# v1.net
KiCad netlist of a schematic drawn in EAGLE
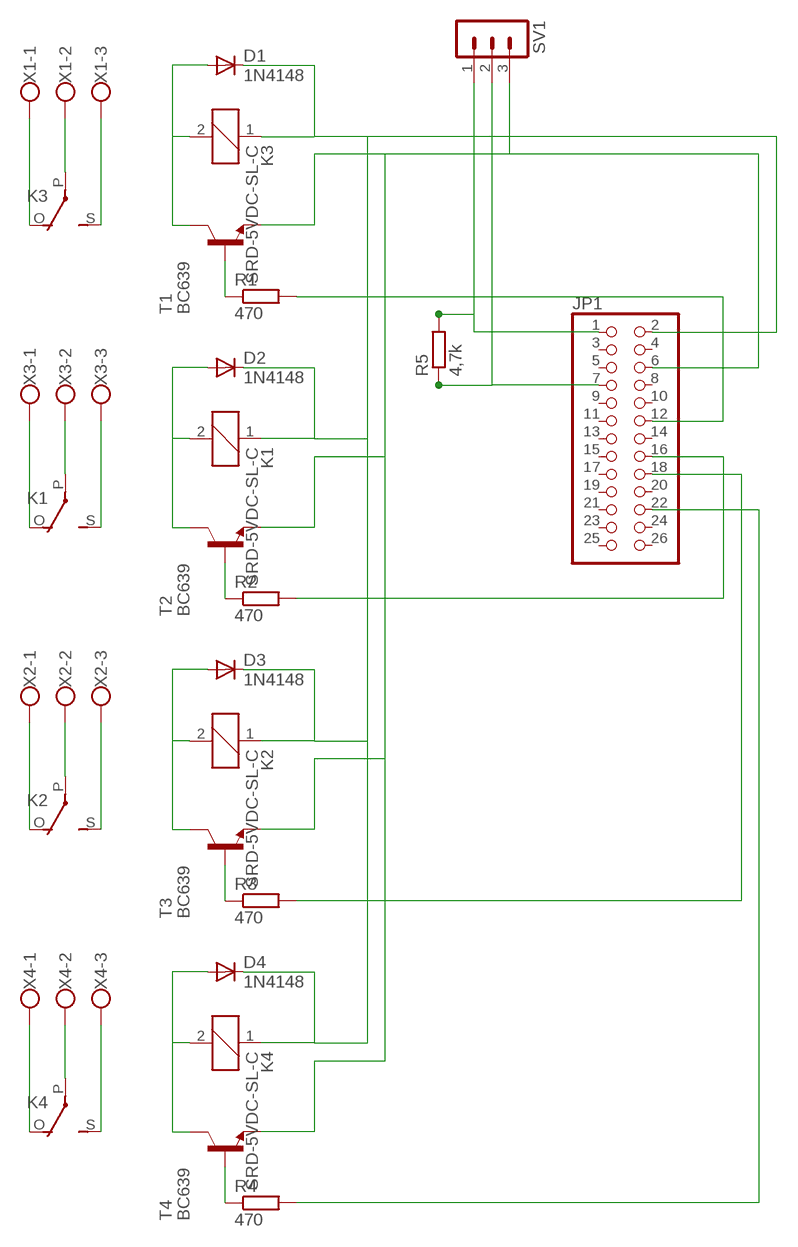
[diagram p0: schematic, sheet 1]

(export (version "E")
  (design (tool "Eeschema 10.0.6"))
  (components
    (comp (ref "D1")
      (value "1N4148")
      (footprint "eagle-import:DO41-10")
      (libsource (lib "eagle-import") (part "1N4004"))
    )
    (comp (ref "D2")
      (value "1N4148")
      (footprint "eagle-import:DO41-10")
      (libsource (lib "eagle-import") (part "1N4004"))
    )
    (comp (ref "D3")
      (value "1N4148")
      (footprint "eagle-import:DO41-10")
      (libsource (lib "eagle-import") (part "1N4004"))
    )
    (comp (ref "D4")
      (value "1N4148")
      (footprint "eagle-import:DO41-10")
      (libsource (lib "eagle-import") (part "1N4004"))
    )
    (comp (ref "JP1")
      (value "PINHD-2X13")
      (footprint "eagle-import:2X13")
      (libsource (lib "eagle-import") (part "PINHD-2X13"))
    )
    (comp (ref "K1")
      (value "SRD-5VDC-SL-C")
      (footprint "eagle-import:ZF112")
      (libsource (lib "eagle-import") (part "ZF112"))
    )
    (comp (ref "K2")
      (value "SRD-5VDC-SL-C")
      (footprint "eagle-import:ZF112")
      (libsource (lib "eagle-import") (part "ZF112"))
    )
    (comp (ref "K3")
      (value "SRD-5VDC-SL-C")
      (footprint "eagle-import:ZF112")
      (libsource (lib "eagle-import") (part "ZF112"))
    )
    (comp (ref "K4")
      (value "SRD-5VDC-SL-C")
      (footprint "eagle-import:ZF112")
      (libsource (lib "eagle-import") (part "ZF112"))
    )
    (comp (ref "R1")
      (value "470")
      (footprint "eagle-import:0204_7")
      (libsource (lib "eagle-import") (part "R-EU_0204/7"))
    )
    (comp (ref "R2")
      (value "470")
      (footprint "eagle-import:0204_7")
      (libsource (lib "eagle-import") (part "R-EU_0204/7"))
    )
    (comp (ref "R3")
      (value "470")
      (footprint "eagle-import:0204_7")
      (libsource (lib "eagle-import") (part "R-EU_0204/7"))
    )
    (comp (ref "R4")
      (value "470")
      (footprint "eagle-import:0204_7")
      (libsource (lib "eagle-import") (part "R-EU_0204/7"))
    )
    (comp (ref "R5")
      (value "4,7k")
      (footprint "eagle-import:0207_7")
      (libsource (lib "eagle-import") (part "R-EU_0207/7"))
    )
    (comp (ref "SV1")
      (value "MA03-1")
      (footprint "eagle-import:MA03-1")
      (libsource (lib "eagle-import") (part "MA03-1"))
    )
    (comp (ref "T1")
      (value "BC639")
      (footprint "eagle-import:TO92-ECB")
      (libsource (lib "eagle-import") (part "-NPN-TO92-ECBBC639"))
    )
    (comp (ref "T2")
      (value "BC639")
      (footprint "eagle-import:TO92-ECB")
      (libsource (lib "eagle-import") (part "-NPN-TO92-ECBBC639"))
    )
    (comp (ref "T3")
      (value "BC639")
      (footprint "eagle-import:TO92-ECB")
      (libsource (lib "eagle-import") (part "-NPN-TO92-ECBBC639"))
    )
    (comp (ref "T4")
      (value "BC639")
      (footprint "eagle-import:TO92-ECB")
      (libsource (lib "eagle-import") (part "-NPN-TO92-ECBBC639"))
    )
    (comp (ref "X1")
      (value "W237-103")
      (footprint "eagle-import:W237-103")
      (fields (field (name "MPN") "237-103"))
      (libsource (lib "eagle-import") (part "W237-103"))
    )
    (comp (ref "X2")
      (value "W237-103")
      (footprint "eagle-import:W237-103")
      (fields (field (name "MPN") "237-103"))
      (libsource (lib "eagle-import") (part "W237-103"))
    )
    (comp (ref "X3")
      (value "W237-103")
      (footprint "eagle-import:W237-103")
      (fields (field (name "MPN") "237-103"))
      (libsource (lib "eagle-import") (part "W237-103"))
    )
    (comp (ref "X4")
      (value "W237-103")
      (footprint "eagle-import:W237-103")
      (fields (field (name "MPN") "237-103"))
      (libsource (lib "eagle-import") (part "W237-103"))
    )
  )
  (nets
    (net (code "1") (name "Net-(D1-PadA)") (class "Default")
      (node (ref "D1") (pin "A") (pinfunction "A_A") (pintype "passive"))
      (node (ref "K3") (pin "2") (pinfunction "2_2") (pintype "passive"))
      (node (ref "T1") (pin "C") (pinfunction "C_C") (pintype "passive"))
    )
    (net (code "2") (name "Net-(D1-PadC)") (class "Default")
      (node (ref "D1") (pin "C") (pinfunction "C_C") (pintype "passive"))
      (node (ref "D2") (pin "C") (pinfunction "C_C") (pintype "passive"))
      (node (ref "D3") (pin "C") (pinfunction "C_C") (pintype "passive"))
      (node (ref "D4") (pin "C") (pinfunction "C_C") (pintype "passive"))
      (node (ref "JP1") (pin "2") (pinfunction "2_2") (pintype "passive"))
      (node (ref "K1") (pin "1") (pinfunction "1_1") (pintype "passive"))
      (node (ref "K2") (pin "1") (pinfunction "1_1") (pintype "passive"))
      (node (ref "K3") (pin "1") (pinfunction "1_1") (pintype "passive"))
      (node (ref "K4") (pin "1") (pinfunction "1_1") (pintype "passive"))
    )
    (net (code "3") (name "Net-(D2-PadA)") (class "Default")
      (node (ref "D2") (pin "A") (pinfunction "A_A") (pintype "passive"))
      (node (ref "K1") (pin "2") (pinfunction "2_2") (pintype "passive"))
      (node (ref "T2") (pin "C") (pinfunction "C_C") (pintype "passive"))
    )
    (net (code "4") (name "Net-(D3-PadA)") (class "Default")
      (node (ref "D3") (pin "A") (pinfunction "A_A") (pintype "passive"))
      (node (ref "K2") (pin "2") (pinfunction "2_2") (pintype "passive"))
      (node (ref "T3") (pin "C") (pinfunction "C_C") (pintype "passive"))
    )
    (net (code "5") (name "Net-(D4-PadA)") (class "Default")
      (node (ref "D4") (pin "A") (pinfunction "A_A") (pintype "passive"))
      (node (ref "K4") (pin "2") (pinfunction "2_2") (pintype "passive"))
      (node (ref "T4") (pin "C") (pinfunction "C_C") (pintype "passive"))
    )
    (net (code "6") (name "Net-(JP1-Pad1)") (class "Default")
      (node (ref "JP1") (pin "1") (pinfunction "1_1") (pintype "passive"))
      (node (ref "R5") (pin "2") (pinfunction "2_2") (pintype "passive"))
      (node (ref "SV1") (pin "1") (pinfunction "1_1") (pintype "passive"))
    )
    (net (code "7") (name "Net-(JP1-Pad6)") (class "Default")
      (node (ref "JP1") (pin "6") (pinfunction "6_6") (pintype "passive"))
      (node (ref "SV1") (pin "3") (pinfunction "3_3") (pintype "passive"))
      (node (ref "T1") (pin "E") (pinfunction "E_E") (pintype "passive"))
      (node (ref "T2") (pin "E") (pinfunction "E_E") (pintype "passive"))
      (node (ref "T3") (pin "E") (pinfunction "E_E") (pintype "passive"))
      (node (ref "T4") (pin "E") (pinfunction "E_E") (pintype "passive"))
    )
    (net (code "8") (name "Net-(JP1-Pad7)") (class "Default")
      (node (ref "JP1") (pin "7") (pinfunction "7_7") (pintype "passive"))
      (node (ref "R5") (pin "1") (pinfunction "1_1") (pintype "passive"))
      (node (ref "SV1") (pin "2") (pinfunction "2_2") (pintype "passive"))
    )
    (net (code "9") (name "Net-(JP1-Pad12)") (class "Default")
      (node (ref "JP1") (pin "12") (pinfunction "12_12") (pintype "passive"))
      (node (ref "R1") (pin "2") (pinfunction "2_2") (pintype "passive"))
    )
    (net (code "10") (name "Net-(JP1-Pad16)") (class "Default")
      (node (ref "JP1") (pin "16") (pinfunction "16_16") (pintype "passive"))
      (node (ref "R2") (pin "2") (pinfunction "2_2") (pintype "passive"))
    )
    (net (code "11") (name "Net-(JP1-Pad18)") (class "Default")
      (node (ref "JP1") (pin "18") (pinfunction "18_18") (pintype "passive"))
      (node (ref "R3") (pin "2") (pinfunction "2_2") (pintype "passive"))
    )
    (net (code "12") (name "Net-(JP1-Pad22)") (class "Default")
      (node (ref "JP1") (pin "22") (pinfunction "22_22") (pintype "passive"))
      (node (ref "R4") (pin "2") (pinfunction "2_2") (pintype "passive"))
    )
    (net (code "13") (name "Net-(R1-Pad1)") (class "Default")
      (node (ref "R1") (pin "1") (pinfunction "1_1") (pintype "passive"))
      (node (ref "T1") (pin "B") (pinfunction "B_B") (pintype "passive"))
    )
    (net (code "14") (name "Net-(R2-Pad1)") (class "Default")
      (node (ref "R2") (pin "1") (pinfunction "1_1") (pintype "passive"))
      (node (ref "T2") (pin "B") (pinfunction "B_B") (pintype "passive"))
    )
    (net (code "15") (name "Net-(R3-Pad1)") (class "Default")
      (node (ref "R3") (pin "1") (pinfunction "1_1") (pintype "passive"))
      (node (ref "T3") (pin "B") (pinfunction "B_B") (pintype "passive"))
    )
    (net (code "16") (name "Net-(R4-Pad1)") (class "Default")
      (node (ref "R4") (pin "1") (pinfunction "1_1") (pintype "passive"))
      (node (ref "T4") (pin "B") (pinfunction "B_B") (pintype "passive"))
    )
    (net (code "17") (name "Net-(X1A-KL)") (class "Default")
      (node (ref "K3") (pin "O") (pinfunction "O_O") (pintype "passive"))
      (node (ref "X1") (pin "1") (pinfunction "KL_1") (pintype "passive"))
    )
    (net (code "18") (name "Net-(X1B-KL)") (class "Default")
      (node (ref "K3") (pin "P") (pinfunction "P_P") (pintype "passive"))
      (node (ref "X1") (pin "2") (pinfunction "KL_2") (pintype "passive"))
    )
    (net (code "19") (name "Net-(X1C-KL)") (class "Default")
      (node (ref "K3") (pin "S") (pinfunction "S_S") (pintype "passive"))
      (node (ref "X1") (pin "3") (pinfunction "KL_3") (pintype "passive"))
    )
    (net (code "20") (name "Net-(X2A-KL)") (class "Default")
      (node (ref "K2") (pin "O") (pinfunction "O_O") (pintype "passive"))
      (node (ref "X2") (pin "1") (pinfunction "KL_1") (pintype "passive"))
    )
    (net (code "21") (name "Net-(X2B-KL)") (class "Default")
      (node (ref "K2") (pin "P") (pinfunction "P_P") (pintype "passive"))
      (node (ref "X2") (pin "2") (pinfunction "KL_2") (pintype "passive"))
    )
    (net (code "22") (name "Net-(X2C-KL)") (class "Default")
      (node (ref "K2") (pin "S") (pinfunction "S_S") (pintype "passive"))
      (node (ref "X2") (pin "3") (pinfunction "KL_3") (pintype "passive"))
    )
    (net (code "23") (name "Net-(X3A-KL)") (class "Default")
      (node (ref "K1") (pin "O") (pinfunction "O_O") (pintype "passive"))
      (node (ref "X3") (pin "1") (pinfunction "KL_1") (pintype "passive"))
    )
    (net (code "24") (name "Net-(X3B-KL)") (class "Default")
      (node (ref "K1") (pin "P") (pinfunction "P_P") (pintype "passive"))
      (node (ref "X3") (pin "2") (pinfunction "KL_2") (pintype "passive"))
    )
    (net (code "25") (name "Net-(X3C-KL)") (class "Default")
      (node (ref "K1") (pin "S") (pinfunction "S_S") (pintype "passive"))
      (node (ref "X3") (pin "3") (pinfunction "KL_3") (pintype "passive"))
    )
    (net (code "26") (name "Net-(X4A-KL)") (class "Default")
      (node (ref "K4") (pin "O") (pinfunction "O_O") (pintype "passive"))
      (node (ref "X4") (pin "1") (pinfunction "KL_1") (pintype "passive"))
    )
    (net (code "27") (name "Net-(X4B-KL)") (class "Default")
      (node (ref "K4") (pin "P") (pinfunction "P_P") (pintype "passive"))
      (node (ref "X4") (pin "2") (pinfunction "KL_2") (pintype "passive"))
    )
    (net (code "28") (name "Net-(X4C-KL)") (class "Default")
      (node (ref "K4") (pin "S") (pinfunction "S_S") (pintype "passive"))
      (node (ref "X4") (pin "3") (pinfunction "KL_3") (pintype "passive"))
    )
    (net (code "29") (name "unconnected-(JP1-Pad3)") (class "Default")
      (node (ref "JP1") (pin "3") (pinfunction "3_3") (pintype "passive"))
    )
    (net (code "30") (name "unconnected-(JP1-Pad4)") (class "Default")
      (node (ref "JP1") (pin "4") (pinfunction "4_4") (pintype "passive"))
    )
    (net (code "31") (name "unconnected-(JP1-Pad5)") (class "Default")
      (node (ref "JP1") (pin "5") (pinfunction "5_5") (pintype "passive"))
    )
    (net (code "32") (name "unconnected-(JP1-Pad8)") (class "Default")
      (node (ref "JP1") (pin "8") (pinfunction "8_8") (pintype "passive"))
    )
    (net (code "33") (name "unconnected-(JP1-Pad9)") (class "Default")
      (node (ref "JP1") (pin "9") (pinfunction "9_9") (pintype "passive"))
    )
    (net (code "34") (name "unconnected-(JP1-Pad10)") (class "Default")
      (node (ref "JP1") (pin "10") (pinfunction "10_10") (pintype "passive"))
    )
    (net (code "35") (name "unconnected-(JP1-Pad11)") (class "Default")
      (node (ref "JP1") (pin "11") (pinfunction "11_11") (pintype "passive"))
    )
    (net (code "36") (name "unconnected-(JP1-Pad13)") (class "Default")
      (node (ref "JP1") (pin "13") (pinfunction "13_13") (pintype "passive"))
    )
    (net (code "37") (name "unconnected-(JP1-Pad14)") (class "Default")
      (node (ref "JP1") (pin "14") (pinfunction "14_14") (pintype "passive"))
    )
    (net (code "38") (name "unconnected-(JP1-Pad15)") (class "Default")
      (node (ref "JP1") (pin "15") (pinfunction "15_15") (pintype "passive"))
    )
    (net (code "39") (name "unconnected-(JP1-Pad17)") (class "Default")
      (node (ref "JP1") (pin "17") (pinfunction "17_17") (pintype "passive"))
    )
    (net (code "40") (name "unconnected-(JP1-Pad19)") (class "Default")
      (node (ref "JP1") (pin "19") (pinfunction "19_19") (pintype "passive"))
    )
    (net (code "41") (name "unconnected-(JP1-Pad20)") (class "Default")
      (node (ref "JP1") (pin "20") (pinfunction "20_20") (pintype "passive"))
    )
    (net (code "42") (name "unconnected-(JP1-Pad21)") (class "Default")
      (node (ref "JP1") (pin "21") (pinfunction "21_21") (pintype "passive"))
    )
    (net (code "43") (name "unconnected-(JP1-Pad23)") (class "Default")
      (node (ref "JP1") (pin "23") (pinfunction "23_23") (pintype "passive"))
    )
    (net (code "44") (name "unconnected-(JP1-Pad24)") (class "Default")
      (node (ref "JP1") (pin "24") (pinfunction "24_24") (pintype "passive"))
    )
    (net (code "45") (name "unconnected-(JP1-Pad25)") (class "Default")
      (node (ref "JP1") (pin "25") (pinfunction "25_25") (pintype "passive"))
    )
    (net (code "46") (name "unconnected-(JP1-Pad26)") (class "Default")
      (node (ref "JP1") (pin "26") (pinfunction "26_26") (pintype "passive"))
    )
  )
)
